# STM32F407VG-E.net
KiCad netlist of a schematic drawn in Altium Designer
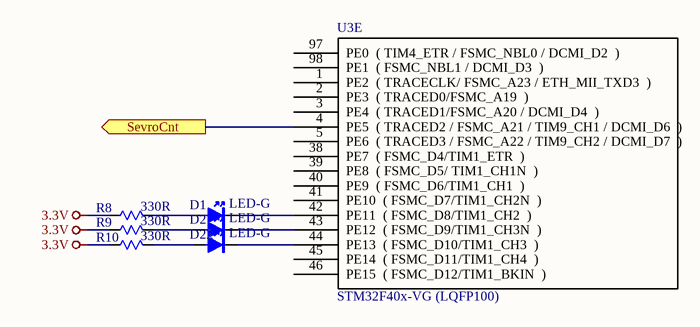
[diagram p0: STM32F407VG-E.SchDoc]

(export (version "E")
  (design (tool "Eeschema 10.0.6"))
  (components
    (comp (ref "D1")
      (value "LED-G")
      (footprint "LED0603")
      (libsource (lib "Passive Components Class") (part "LED"))
    )
    (comp (ref "D2")
      (value "LED-G")
      (footprint "LED0603")
      (libsource (lib "Passive Components Class") (part "LED"))
    )
    (comp (ref "D22")
      (value "LED-G")
      (footprint "LED0603")
      (libsource (lib "Passive Components Class") (part "LED"))
    )
    (comp (ref "R8")
      (value "330R")
      (footprint "R0603-S")
      (description "Resistor")
      (fields (field (name "PUBLISHER") "Altium Limited"))
      (libsource (lib "UP-Robot") (part "Res"))
    )
    (comp (ref "R9")
      (value "330R")
      (footprint "R0603-S")
      (description "Resistor")
      (fields (field (name "PUBLISHER") "Altium Limited"))
      (libsource (lib "UP-Robot") (part "Res"))
    )
    (comp (ref "R10")
      (value "330R")
      (footprint "R0603-S")
      (description "Resistor")
      (fields (field (name "PUBLISHER") "Altium Limited"))
      (libsource (lib "UP-Robot") (part "Res"))
    )
    (comp (ref "U3")
      (value "STM32F40x-VG (LQFP100)")
      (footprint "LQFP100_N")
      (libsource (lib "Microcontrollers Class") (part "STM32F40x-VG"))
    )
  )
  (nets
    (net (code "1") (name "/SevroCnt") (class "Default")
      (node (ref "U3") (pin "4") (pinfunction "PE5__(_TRACED2_/_FSMC_A21_/_TIM9_CH1_/_DCMI_D6__)_4") (pintype "passive"))
    )
    (net (code "2") (name "3.3V") (class "Default")
      (node (ref "R10") (pin "2") (pinfunction "2_2") (pintype "passive"))
      (node (ref "R8") (pin "2") (pinfunction "2_2") (pintype "passive"))
      (node (ref "R9") (pin "2") (pinfunction "2_2") (pintype "passive"))
    )
    (net (code "3") (name "Net-(D1-A)") (class "Default")
      (node (ref "D1") (pin "1") (pinfunction "A_1") (pintype "passive"))
      (node (ref "R8") (pin "1") (pinfunction "1_1") (pintype "passive"))
    )
    (net (code "4") (name "Net-(D1-K)") (class "Default")
      (node (ref "D1") (pin "2") (pinfunction "K_2") (pintype "passive"))
      (node (ref "U3") (pin "42") (pinfunction "PE11__(_FSMC_D8/TIM1_CH2__)_42") (pintype "passive"))
    )
    (net (code "5") (name "Net-(D2-A)") (class "Default")
      (node (ref "D2") (pin "1") (pinfunction "A_1") (pintype "passive"))
      (node (ref "R9") (pin "1") (pinfunction "1_1") (pintype "passive"))
    )
    (net (code "6") (name "Net-(D2-K)") (class "Default")
      (node (ref "D2") (pin "2") (pinfunction "K_2") (pintype "passive"))
      (node (ref "U3") (pin "43") (pinfunction "PE12__(_FSMC_D9/TIM1_CH3N__)_43") (pintype "passive"))
    )
    (net (code "7") (name "Net-(D22-A)") (class "Default")
      (node (ref "D22") (pin "1") (pinfunction "A_1") (pintype "passive"))
      (node (ref "R10") (pin "1") (pinfunction "1_1") (pintype "passive"))
    )
    (net (code "8") (name "Net-(D22-K)") (class "Default")
      (node (ref "D22") (pin "2") (pinfunction "K_2") (pintype "passive"))
      (node (ref "U3") (pin "44") (pinfunction "PE13__(_FSMC_D10/TIM1_CH3__)_44") (pintype "passive"))
    )
    (net (code "9") (name "unconnected-(U3E-PE0__(_TIM4_ETR_{slash}_FSMC_NBL0_{slash}_DCMI_D2__)-Pad97)") (class "Default")
      (node (ref "U3") (pin "97") (pinfunction "PE0__(_TIM4_ETR_/_FSMC_NBL0_/_DCMI_D2__)_97") (pintype "passive"))
    )
    (net (code "10") (name "unconnected-(U3E-PE1__(_FSMC_NBL1_{slash}_DCMI_D3__)-Pad98)") (class "Default")
      (node (ref "U3") (pin "98") (pinfunction "PE1__(_FSMC_NBL1_/_DCMI_D3__)_98") (pintype "passive"))
    )
    (net (code "11") (name "unconnected-(U3E-PE2__(_TRACECLK{slash}_FSMC_A23_{slash}_ETH_MII_TXD3__)-Pad1)") (class "Default")
      (node (ref "U3") (pin "1") (pinfunction "PE2__(_TRACECLK/_FSMC_A23_/_ETH_MII_TXD3__)_1") (pintype "passive"))
    )
    (net (code "12") (name "unconnected-(U3E-PE3__(_TRACED0{slash}FSMC_A19__)-Pad2)") (class "Default")
      (node (ref "U3") (pin "2") (pinfunction "PE3__(_TRACED0/FSMC_A19__)_2") (pintype "passive"))
    )
    (net (code "13") (name "unconnected-(U3E-PE4__(_TRACED1{slash}FSMC_A20_{slash}_DCMI_D4__)-Pad3)") (class "Default")
      (node (ref "U3") (pin "3") (pinfunction "PE4__(_TRACED1/FSMC_A20_/_DCMI_D4__)_3") (pintype "passive"))
    )
    (net (code "14") (name "unconnected-(U3E-PE6__(_TRACED3_{slash}_FSMC_A22_{slash}_TIM9_CH2_{slash}_DCMI_D7__)-Pad5)") (class "Default")
      (node (ref "U3") (pin "5") (pinfunction "PE6__(_TRACED3_/_FSMC_A22_/_TIM9_CH2_/_DCMI_D7__)_5") (pintype "passive"))
    )
    (net (code "15") (name "unconnected-(U3E-PE7__(_FSMC_D4{slash}TIM1_ETR__)-Pad38)") (class "Default")
      (node (ref "U3") (pin "38") (pinfunction "PE7__(_FSMC_D4/TIM1_ETR__)_38") (pintype "passive"))
    )
    (net (code "16") (name "unconnected-(U3E-PE8__(_FSMC_D5{slash}_TIM1_CH1N__)-Pad39)") (class "Default")
      (node (ref "U3") (pin "39") (pinfunction "PE8__(_FSMC_D5/_TIM1_CH1N__)_39") (pintype "passive"))
    )
    (net (code "17") (name "unconnected-(U3E-PE9__(_FSMC_D6{slash}TIM1_CH1__)-Pad40)") (class "Default")
      (node (ref "U3") (pin "40") (pinfunction "PE9__(_FSMC_D6/TIM1_CH1__)_40") (pintype "passive"))
    )
    (net (code "18") (name "unconnected-(U3E-PE10__(_FSMC_D7{slash}TIM1_CH2N__)-Pad41)") (class "Default")
      (node (ref "U3") (pin "41") (pinfunction "PE10__(_FSMC_D7/TIM1_CH2N__)_41") (pintype "passive"))
    )
    (net (code "19") (name "unconnected-(U3E-PE14__(_FSMC_D11{slash}TIM1_CH4__)-Pad45)") (class "Default")
      (node (ref "U3") (pin "45") (pinfunction "PE14__(_FSMC_D11/TIM1_CH4__)_45") (pintype "passive"))
    )
    (net (code "20") (name "unconnected-(U3E-PE15__(_FSMC_D12{slash}TIM1_BKIN__)-Pad46)") (class "Default")
      (node (ref "U3") (pin "46") (pinfunction "PE15__(_FSMC_D12/TIM1_BKIN__)_46") (pintype "passive"))
    )
  )
)
